# MiP_Mini-Pack.net
KiCad netlist of a schematic drawn in EAGLE
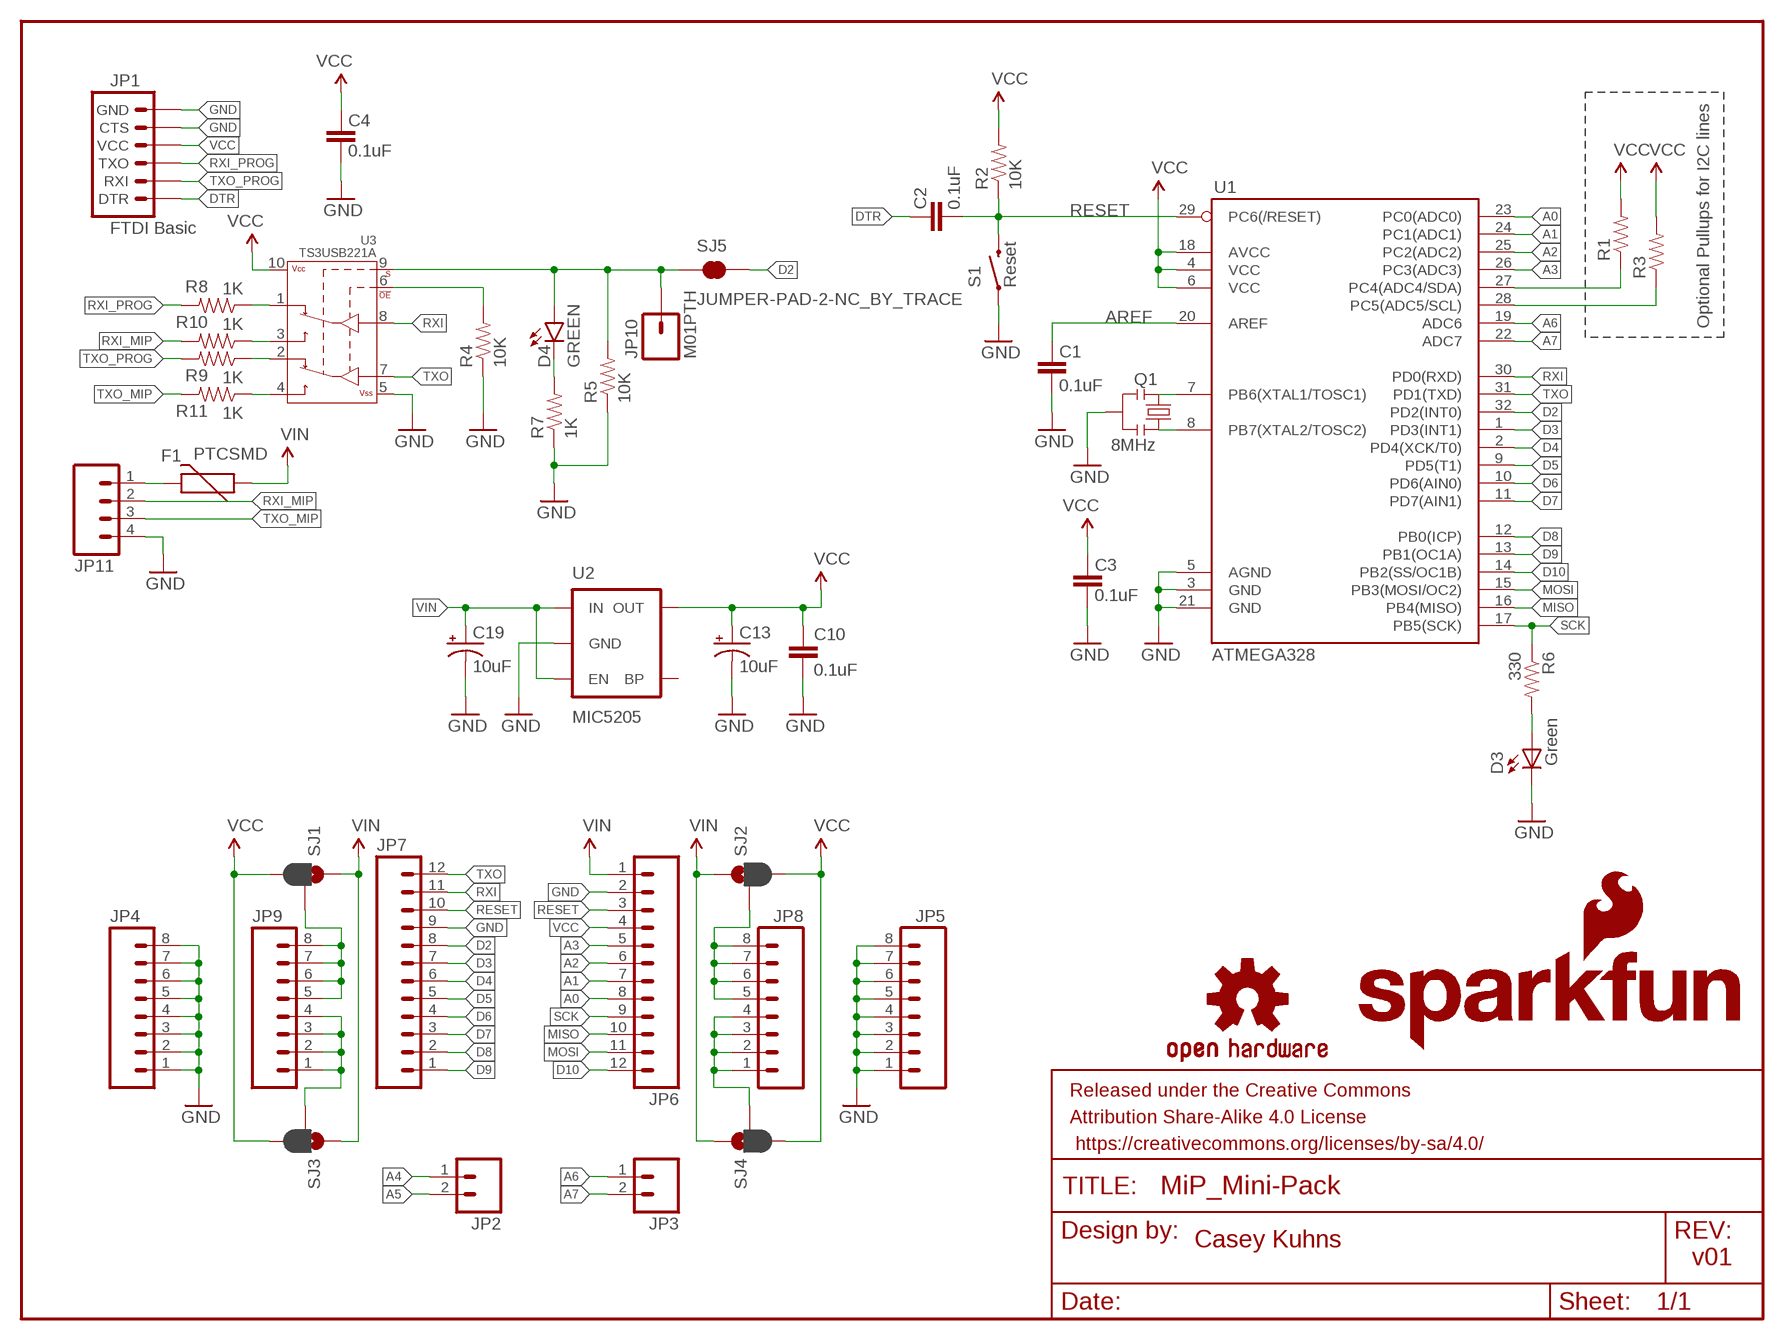
[diagram p0: schematic, sheet 1]

(export (version "E")
  (design (tool "Eeschema 10.0.6"))
  (components
    (comp (ref "C1")
      (value "0.1uF")
      (footprint "eagle-import:0603-CAP")
      (libsource (lib "eagle-import") (part "CAP0603-CAP"))
    )
    (comp (ref "C2")
      (value "0.1uF")
      (footprint "eagle-import:0603-CAP")
      (libsource (lib "eagle-import") (part "CAP0603-CAP"))
    )
    (comp (ref "C3")
      (value "0.1uF")
      (footprint "eagle-import:0603-CAP")
      (libsource (lib "eagle-import") (part "CAP0603-CAP"))
    )
    (comp (ref "C4")
      (value "0.1uF")
      (footprint "eagle-import:0603-CAP")
      (libsource (lib "eagle-import") (part "CAP0603-CAP"))
    )
    (comp (ref "C10")
      (value "0.1uF")
      (footprint "eagle-import:0603-CAP")
      (libsource (lib "eagle-import") (part "CAP0603-CAP"))
    )
    (comp (ref "C13")
      (value "10uF")
      (footprint "eagle-import:EIA3216")
      (libsource (lib "eagle-import") (part "CAP_POL1206"))
    )
    (comp (ref "C19")
      (value "10uF")
      (footprint "eagle-import:EIA3216")
      (libsource (lib "eagle-import") (part "CAP_POL1206"))
    )
    (comp (ref "D3")
      (value "Green")
      (footprint "eagle-import:0603-LED-ALT1")
      (libsource (lib "eagle-import") (part "LED"))
    )
    (comp (ref "D4")
      (value "GREEN")
      (footprint "eagle-import:LED-0603")
      (libsource (lib "eagle-import") (part "LED-GREEN0603"))
    )
    (comp (ref "F1")
      (value "PTCSMD")
      (footprint "eagle-import:PTC-1206")
      (libsource (lib "eagle-import") (part "PTCSMD"))
    )
    (comp (ref "FRAME1")
      (value "FRAME-LETTER")
      (footprint "eagle-import:CREATIVE_COMMONS")
      (libsource (lib "eagle-import") (part "FRAME-LETTER"))
    )
    (comp (ref "JP1")
      (value "FTDI Basic")
      (footprint "eagle-import:1X06")
      (libsource (lib "eagle-import") (part "ARDUINO_SERIAL_PROGRAMPTH"))
    )
    (comp (ref "JP2")
      (value "M02PTH")
      (footprint "eagle-import:1X02")
      (libsource (lib "eagle-import") (part "M02PTH"))
    )
    (comp (ref "JP3")
      (value "M02PTH")
      (footprint "eagle-import:1X02")
      (libsource (lib "eagle-import") (part "M02PTH"))
    )
    (comp (ref "JP4")
      (value "M081X08")
      (footprint "eagle-import:1X08")
      (libsource (lib "eagle-import") (part "M081X08"))
    )
    (comp (ref "JP5")
      (value "M081X08")
      (footprint "eagle-import:1X08")
      (libsource (lib "eagle-import") (part "M081X08"))
    )
    (comp (ref "JP6")
      (value "M12PTH")
      (footprint "eagle-import:1X12")
      (libsource (lib "eagle-import") (part "M12PTH"))
    )
    (comp (ref "JP7")
      (value "M12PTH")
      (footprint "eagle-import:1X12")
      (libsource (lib "eagle-import") (part "M12PTH"))
    )
    (comp (ref "JP8")
      (value "M081X08")
      (footprint "eagle-import:1X08")
      (libsource (lib "eagle-import") (part "M081X08"))
    )
    (comp (ref "JP9")
      (value "M081X08")
      (footprint "eagle-import:1X08")
      (libsource (lib "eagle-import") (part "M081X08"))
    )
    (comp (ref "JP10")
      (value "M01PTH")
      (footprint "eagle-import:1X01")
      (libsource (lib "eagle-import") (part "M01PTH"))
    )
    (comp (ref "JP11")
      (value "M04JST")
      (footprint "eagle-import:1X04-1.5MM_JST")
      (libsource (lib "eagle-import") (part "M04JST"))
    )
    (comp (ref "LOGO1")
      (value "SFE_LOGO_NAME_FLAME.1_INCH")
      (footprint "eagle-import:SFE_LOGO_NAME_FLAME_.1")
      (libsource (lib "eagle-import") (part "SFE_LOGO_NAME_FLAME.1_INCH"))
    )
    (comp (ref "LOGO2")
      (value "OSHW-LOGOS")
      (footprint "eagle-import:OSHW-LOGO-S")
      (libsource (lib "eagle-import") (part "OSHW-LOGOS"))
    )
    (comp (ref "Q1")
      (value "8MHz")
      (footprint "eagle-import:RESONATOR-SMD")
      (libsource (lib "eagle-import") (part "RESONATOR8MHZ"))
    )
    (comp (ref "R1")
      (value "RESISTOR0603-RES")
      (footprint "eagle-import:0603-RES")
      (libsource (lib "eagle-import") (part "RESISTOR0603-RES"))
    )
    (comp (ref "R2")
      (value "10K")
      (footprint "eagle-import:0603-RES")
      (libsource (lib "eagle-import") (part "RESISTOR0603-RES"))
    )
    (comp (ref "R3")
      (value "RESISTOR0603-RES")
      (footprint "eagle-import:0603-RES")
      (libsource (lib "eagle-import") (part "RESISTOR0603-RES"))
    )
    (comp (ref "R4")
      (value "10K")
      (footprint "eagle-import:0603-RES")
      (libsource (lib "eagle-import") (part "10KOHM1/10W1%(0603)0603"))
    )
    (comp (ref "R5")
      (value "10K")
      (footprint "eagle-import:0603-RES")
      (libsource (lib "eagle-import") (part "10KOHM1/10W1%(0603)0603"))
    )
    (comp (ref "R6")
      (value "330")
      (footprint "eagle-import:0603-RES")
      (libsource (lib "eagle-import") (part "RESISTOR0603-RES"))
    )
    (comp (ref "R7")
      (value "1K")
      (footprint "eagle-import:0603-RES")
      (libsource (lib "eagle-import") (part "1KOHM1/10W1%(0603)"))
    )
    (comp (ref "R8")
      (value "1K")
      (footprint "eagle-import:0603-RES")
      (libsource (lib "eagle-import") (part "1KOHM1/10W1%(0603)"))
    )
    (comp (ref "R9")
      (value "1K")
      (footprint "eagle-import:0603-RES")
      (libsource (lib "eagle-import") (part "1KOHM1/10W1%(0603)"))
    )
    (comp (ref "R10")
      (value "1K")
      (footprint "eagle-import:0603-RES")
      (libsource (lib "eagle-import") (part "1KOHM1/10W1%(0603)"))
    )
    (comp (ref "R11")
      (value "1K")
      (footprint "eagle-import:0603-RES")
      (libsource (lib "eagle-import") (part "1KOHM1/10W1%(0603)"))
    )
    (comp (ref "S1")
      (value "Reset")
      (footprint "eagle-import:TACTILE-SWITCH-SMD-ALT01")
      (libsource (lib "eagle-import") (part "SWITCH-MOMENTARY-2SMD-ALT01"))
    )
    (comp (ref "SJ1")
      (value "JUMPER-PAD-3-2OF3_NC_BY_PASTE")
      (footprint "eagle-import:PAD-JUMPER-3-2OF3_NC_BY_PASTE_YES_SILK_FULL_BOX")
      (libsource (lib "eagle-import") (part "JUMPER-PAD-3-2OF3_NC_BY_PASTE"))
    )
    (comp (ref "SJ2")
      (value "JUMPER-PAD-3-2OF3_NC_BY_PASTE")
      (footprint "eagle-import:PAD-JUMPER-3-2OF3_NC_BY_PASTE_YES_SILK_FULL_BOX")
      (libsource (lib "eagle-import") (part "JUMPER-PAD-3-2OF3_NC_BY_PASTE"))
    )
    (comp (ref "SJ3")
      (value "JUMPER-PAD-3-2OF3_NC_BY_PASTE")
      (footprint "eagle-import:PAD-JUMPER-3-2OF3_NC_BY_PASTE_YES_SILK_FULL_BOX")
      (libsource (lib "eagle-import") (part "JUMPER-PAD-3-2OF3_NC_BY_PASTE"))
    )
    (comp (ref "SJ4")
      (value "JUMPER-PAD-3-2OF3_NC_BY_PASTE")
      (footprint "eagle-import:PAD-JUMPER-3-2OF3_NC_BY_PASTE_YES_SILK_FULL_BOX")
      (libsource (lib "eagle-import") (part "JUMPER-PAD-3-2OF3_NC_BY_PASTE"))
    )
    (comp (ref "SJ5")
      (value "JUMPER-PAD-2-NC_BY_TRACE")
      (footprint "eagle-import:PAD-JUMPER-2-NC_BY_TRACE_YES_SILK")
      (libsource (lib "eagle-import") (part "JUMPER-PAD-2-NC_BY_TRACE"))
    )
    (comp (ref "U1")
      (value "ATMEGA328")
      (footprint "eagle-import:TQFP32-08")
      (libsource (lib "eagle-import") (part "ATMEGA168"))
    )
    (comp (ref "U2")
      (value "MIC5205")
      (footprint "eagle-import:SOT23-5")
      (libsource (lib "eagle-import") (part "V_REG_LDOSMD"))
    )
    (comp (ref "U3")
      (value "TS3USB221A")
      (footprint "eagle-import:QFN-10-RSE")
      (libsource (lib "eagle-import") (part "TS3USB221A"))
    )
  )
  (nets
    (net (code "1") (name "/AREF") (class "Default")
      (node (ref "C1") (pin "2") (pinfunction "2_2") (pintype "passive"))
      (node (ref "U1") (pin "20") (pinfunction "AREF_20") (pintype "bidirectional"))
    )
    (net (code "2") (name "A0") (class "Default")
      (node (ref "JP6") (pin "8") (pinfunction "8_8") (pintype "passive"))
      (node (ref "U1") (pin "23") (pinfunction "PC0(ADC0)_23") (pintype "bidirectional"))
    )
    (net (code "3") (name "A1") (class "Default")
      (node (ref "JP6") (pin "7") (pinfunction "7_7") (pintype "passive"))
      (node (ref "U1") (pin "24") (pinfunction "PC1(ADC1)_24") (pintype "bidirectional"))
    )
    (net (code "4") (name "A2") (class "Default")
      (node (ref "JP6") (pin "6") (pinfunction "6_6") (pintype "passive"))
      (node (ref "U1") (pin "25") (pinfunction "PC2(ADC2)_25") (pintype "bidirectional"))
    )
    (net (code "5") (name "A3") (class "Default")
      (node (ref "JP6") (pin "5") (pinfunction "5_5") (pintype "passive"))
      (node (ref "U1") (pin "26") (pinfunction "PC3(ADC3)_26") (pintype "bidirectional"))
    )
    (net (code "6") (name "A4") (class "Default")
      (node (ref "JP2") (pin "1") (pinfunction "1_1") (pintype "passive"))
      (node (ref "R1") (pin "1") (pinfunction "1_1") (pintype "passive"))
      (node (ref "U1") (pin "27") (pinfunction "PC4(ADC4/SDA)_27") (pintype "bidirectional"))
    )
    (net (code "7") (name "A5") (class "Default")
      (node (ref "JP2") (pin "2") (pinfunction "2_2") (pintype "passive"))
      (node (ref "R3") (pin "1") (pinfunction "1_1") (pintype "passive"))
      (node (ref "U1") (pin "28") (pinfunction "PC5(ADC5/SCL)_28") (pintype "bidirectional"))
    )
    (net (code "8") (name "A6") (class "Default")
      (node (ref "JP3") (pin "1") (pinfunction "1_1") (pintype "passive"))
      (node (ref "U1") (pin "19") (pinfunction "ADC6_19") (pintype "bidirectional"))
    )
    (net (code "9") (name "A7") (class "Default")
      (node (ref "JP3") (pin "2") (pinfunction "2_2") (pintype "passive"))
      (node (ref "U1") (pin "22") (pinfunction "ADC7_22") (pintype "bidirectional"))
    )
    (net (code "10") (name "D2") (class "Default")
      (node (ref "JP7") (pin "8") (pinfunction "8_8") (pintype "passive"))
      (node (ref "SJ5") (pin "2") (pinfunction "2_2") (pintype "passive"))
      (node (ref "U1") (pin "32") (pinfunction "PD2(INT0)_32") (pintype "bidirectional"))
    )
    (net (code "11") (name "D3") (class "Default")
      (node (ref "JP7") (pin "7") (pinfunction "7_7") (pintype "passive"))
      (node (ref "U1") (pin "1") (pinfunction "PD3(INT1)_1") (pintype "bidirectional"))
    )
    (net (code "12") (name "D4") (class "Default")
      (node (ref "JP7") (pin "6") (pinfunction "6_6") (pintype "passive"))
      (node (ref "U1") (pin "2") (pinfunction "PD4(XCK/T0)_2") (pintype "bidirectional"))
    )
    (net (code "13") (name "D5") (class "Default")
      (node (ref "JP7") (pin "5") (pinfunction "5_5") (pintype "passive"))
      (node (ref "U1") (pin "9") (pinfunction "PD5(T1)_9") (pintype "bidirectional"))
    )
    (net (code "14") (name "D6") (class "Default")
      (node (ref "JP7") (pin "4") (pinfunction "4_4") (pintype "passive"))
      (node (ref "U1") (pin "10") (pinfunction "PD6(AIN0)_10") (pintype "bidirectional"))
    )
    (net (code "15") (name "D7") (class "Default")
      (node (ref "JP7") (pin "3") (pinfunction "3_3") (pintype "passive"))
      (node (ref "U1") (pin "11") (pinfunction "PD7(AIN1)_11") (pintype "bidirectional"))
    )
    (net (code "16") (name "D8") (class "Default")
      (node (ref "JP7") (pin "2") (pinfunction "2_2") (pintype "passive"))
      (node (ref "U1") (pin "12") (pinfunction "PB0(ICP)_12") (pintype "bidirectional"))
    )
    (net (code "17") (name "D9") (class "Default")
      (node (ref "JP7") (pin "1") (pinfunction "1_1") (pintype "passive"))
      (node (ref "U1") (pin "13") (pinfunction "PB1(OC1A)_13") (pintype "bidirectional"))
    )
    (net (code "18") (name "D10") (class "Default")
      (node (ref "JP6") (pin "12") (pinfunction "12_12") (pintype "passive"))
      (node (ref "U1") (pin "14") (pinfunction "PB2(SS/OC1B)_14") (pintype "bidirectional"))
    )
    (net (code "19") (name "DTR") (class "Default")
      (node (ref "C2") (pin "2") (pinfunction "2_2") (pintype "passive"))
      (node (ref "JP1") (pin "1") (pinfunction "DTR_1") (pintype "passive"))
    )
    (net (code "20") (name "GND") (class "Default")
      (node (ref "C1") (pin "1") (pinfunction "1_1") (pintype "passive"))
      (node (ref "C10") (pin "2") (pinfunction "2_2") (pintype "passive"))
      (node (ref "C13") (pin "C") (pinfunction "-_C") (pintype "passive"))
      (node (ref "C19") (pin "C") (pinfunction "-_C") (pintype "passive"))
      (node (ref "C3") (pin "1") (pinfunction "1_1") (pintype "passive"))
      (node (ref "C4") (pin "1") (pinfunction "1_1") (pintype "passive"))
      (node (ref "D3") (pin "C") (pinfunction "C_C") (pintype "passive"))
      (node (ref "JP1") (pin "5") (pinfunction "CTS_5") (pintype "passive"))
      (node (ref "JP1") (pin "6") (pinfunction "GND_6") (pintype "passive"))
      (node (ref "JP11") (pin "4") (pinfunction "4_4") (pintype "passive"))
      (node (ref "JP4") (pin "1") (pinfunction "1_1") (pintype "passive"))
      (node (ref "JP4") (pin "2") (pinfunction "2_2") (pintype "passive"))
      (node (ref "JP4") (pin "3") (pinfunction "3_3") (pintype "passive"))
      (node (ref "JP4") (pin "4") (pinfunction "4_4") (pintype "passive"))
      (node (ref "JP4") (pin "5") (pinfunction "5_5") (pintype "passive"))
      (node (ref "JP4") (pin "6") (pinfunction "6_6") (pintype "passive"))
      (node (ref "JP4") (pin "7") (pinfunction "7_7") (pintype "passive"))
      (node (ref "JP4") (pin "8") (pinfunction "8_8") (pintype "passive"))
      (node (ref "JP5") (pin "1") (pinfunction "1_1") (pintype "passive"))
      (node (ref "JP5") (pin "2") (pinfunction "2_2") (pintype "passive"))
      (node (ref "JP5") (pin "3") (pinfunction "3_3") (pintype "passive"))
      (node (ref "JP5") (pin "4") (pinfunction "4_4") (pintype "passive"))
      (node (ref "JP5") (pin "5") (pinfunction "5_5") (pintype "passive"))
      (node (ref "JP5") (pin "6") (pinfunction "6_6") (pintype "passive"))
      (node (ref "JP5") (pin "7") (pinfunction "7_7") (pintype "passive"))
      (node (ref "JP5") (pin "8") (pinfunction "8_8") (pintype "passive"))
      (node (ref "JP6") (pin "2") (pinfunction "2_2") (pintype "passive"))
      (node (ref "JP7") (pin "9") (pinfunction "9_9") (pintype "passive"))
      (node (ref "Q1") (pin "2") (pinfunction "2_2") (pintype "passive"))
      (node (ref "R4") (pin "1") (pinfunction "1_1") (pintype "passive"))
      (node (ref "R5") (pin "1") (pinfunction "1_1") (pintype "passive"))
      (node (ref "R7") (pin "1") (pinfunction "1_1") (pintype "passive"))
      (node (ref "S1") (pin "1") (pinfunction "1_1") (pintype "passive"))
      (node (ref "S1") (pin "2") (pinfunction "1_2") (pintype "passive"))
      (node (ref "U1") (pin "21") (pinfunction "GND_21") (pintype "bidirectional"))
      (node (ref "U1") (pin "3") (pinfunction "GND_3") (pintype "bidirectional"))
      (node (ref "U1") (pin "5") (pinfunction "AGND_5") (pintype "bidirectional"))
      (node (ref "U2") (pin "2") (pinfunction "GND_2") (pintype "input"))
      (node (ref "U3") (pin "5") (pinfunction "VSS_5") (pintype "bidirectional"))
    )
    (net (code "21") (name "MISO") (class "Default")
      (node (ref "JP6") (pin "10") (pinfunction "10_10") (pintype "passive"))
      (node (ref "U1") (pin "16") (pinfunction "PB4(MISO)_16") (pintype "bidirectional"))
    )
    (net (code "22") (name "MOSI") (class "Default")
      (node (ref "JP6") (pin "11") (pinfunction "11_11") (pintype "passive"))
      (node (ref "U1") (pin "15") (pinfunction "PB3(MOSI/OC2)_15") (pintype "bidirectional"))
    )
    (net (code "23") (name "Net-(D3-PadA)") (class "Default")
      (node (ref "D3") (pin "A") (pinfunction "A_A") (pintype "passive"))
      (node (ref "R6") (pin "2") (pinfunction "2_2") (pintype "passive"))
    )
    (net (code "24") (name "Net-(D4-PadC)") (class "Default")
      (node (ref "D4") (pin "C") (pinfunction "C_C") (pintype "passive"))
      (node (ref "R7") (pin "2") (pinfunction "2_2") (pintype "passive"))
    )
    (net (code "25") (name "Net-(F1-Pad2)") (class "Default")
      (node (ref "F1") (pin "2") (pinfunction "2_2") (pintype "bidirectional"))
      (node (ref "JP11") (pin "1") (pinfunction "1_1") (pintype "passive"))
    )
    (net (code "26") (name "Net-(JP8-Pad1)") (class "Default")
      (node (ref "JP8") (pin "1") (pinfunction "1_1") (pintype "passive"))
      (node (ref "JP8") (pin "2") (pinfunction "2_2") (pintype "passive"))
      (node (ref "JP8") (pin "3") (pinfunction "3_3") (pintype "passive"))
      (node (ref "JP8") (pin "4") (pinfunction "4_4") (pintype "passive"))
      (node (ref "SJ4") (pin "2") (pinfunction "2_2") (pintype "passive"))
    )
    (net (code "27") (name "Net-(JP8-Pad5)") (class "Default")
      (node (ref "JP8") (pin "5") (pinfunction "5_5") (pintype "passive"))
      (node (ref "JP8") (pin "6") (pinfunction "6_6") (pintype "passive"))
      (node (ref "JP8") (pin "7") (pinfunction "7_7") (pintype "passive"))
      (node (ref "JP8") (pin "8") (pinfunction "8_8") (pintype "passive"))
      (node (ref "SJ2") (pin "2") (pinfunction "2_2") (pintype "passive"))
    )
    (net (code "28") (name "Net-(JP9-Pad1)") (class "Default")
      (node (ref "JP9") (pin "1") (pinfunction "1_1") (pintype "passive"))
      (node (ref "JP9") (pin "2") (pinfunction "2_2") (pintype "passive"))
      (node (ref "JP9") (pin "3") (pinfunction "3_3") (pintype "passive"))
      (node (ref "JP9") (pin "4") (pinfunction "4_4") (pintype "passive"))
      (node (ref "SJ3") (pin "2") (pinfunction "2_2") (pintype "passive"))
    )
    (net (code "29") (name "Net-(JP9-Pad5)") (class "Default")
      (node (ref "JP9") (pin "5") (pinfunction "5_5") (pintype "passive"))
      (node (ref "JP9") (pin "6") (pinfunction "6_6") (pintype "passive"))
      (node (ref "JP9") (pin "7") (pinfunction "7_7") (pintype "passive"))
      (node (ref "JP9") (pin "8") (pinfunction "8_8") (pintype "passive"))
      (node (ref "SJ1") (pin "2") (pinfunction "2_2") (pintype "passive"))
    )
    (net (code "30") (name "Net-(U1-PB6(XTAL1{slash}TOSC1))") (class "Default")
      (node (ref "Q1") (pin "1") (pinfunction "1_1") (pintype "passive"))
      (node (ref "U1") (pin "7") (pinfunction "PB6(XTAL1/TOSC1)_7") (pintype "bidirectional"))
    )
    (net (code "31") (name "Net-(U1-PB7(XTAL2{slash}TOSC2))") (class "Default")
      (node (ref "Q1") (pin "3") (pinfunction "3_3") (pintype "passive"))
      (node (ref "U1") (pin "8") (pinfunction "PB7(XTAL2/TOSC2)_8") (pintype "bidirectional"))
    )
    (net (code "32") (name "Net-(U3-1D+)") (class "Default")
      (node (ref "R8") (pin "1") (pinfunction "1_1") (pintype "passive"))
      (node (ref "U3") (pin "1") (pinfunction "1D+_1") (pintype "bidirectional"))
    )
    (net (code "33") (name "Net-(U3-1D-)") (class "Default")
      (node (ref "R9") (pin "1") (pinfunction "1_1") (pintype "passive"))
      (node (ref "U3") (pin "2") (pinfunction "1D-_2") (pintype "bidirectional"))
    )
    (net (code "34") (name "Net-(U3-2D+)") (class "Default")
      (node (ref "R10") (pin "1") (pinfunction "1_1") (pintype "passive"))
      (node (ref "U3") (pin "3") (pinfunction "2D+_3") (pintype "bidirectional"))
    )
    (net (code "35") (name "Net-(U3-2D-)") (class "Default")
      (node (ref "R11") (pin "1") (pinfunction "1_1") (pintype "passive"))
      (node (ref "U3") (pin "4") (pinfunction "2D-_4") (pintype "bidirectional"))
    )
    (net (code "36") (name "Net-(U3-S)") (class "Default")
      (node (ref "D4") (pin "A") (pinfunction "A_A") (pintype "passive"))
      (node (ref "JP10") (pin "1") (pinfunction "1_1") (pintype "passive"))
      (node (ref "R5") (pin "2") (pinfunction "2_2") (pintype "passive"))
      (node (ref "SJ5") (pin "1") (pinfunction "1_1") (pintype "passive"))
      (node (ref "U3") (pin "9") (pinfunction "S_9") (pintype "bidirectional"))
    )
    (net (code "37") (name "Net-(U3-~{OE})") (class "Default")
      (node (ref "R4") (pin "2") (pinfunction "2_2") (pintype "passive"))
      (node (ref "U3") (pin "6") (pinfunction "~{OE}_6") (pintype "bidirectional"))
    )
    (net (code "38") (name "RESET") (class "Default")
      (node (ref "C2") (pin "1") (pinfunction "1_1") (pintype "passive"))
      (node (ref "JP6") (pin "3") (pinfunction "3_3") (pintype "passive"))
      (node (ref "JP7") (pin "10") (pinfunction "10_10") (pintype "passive"))
      (node (ref "R2") (pin "1") (pinfunction "1_1") (pintype "passive"))
      (node (ref "S1") (pin "3") (pinfunction "2_3") (pintype "passive"))
      (node (ref "S1") (pin "4") (pinfunction "2_4") (pintype "passive"))
      (node (ref "U1") (pin "29") (pinfunction "PC6(/RESET)_29") (pintype "bidirectional"))
    )
    (net (code "39") (name "RXI") (class "Default")
      (node (ref "JP7") (pin "11") (pinfunction "11_11") (pintype "passive"))
      (node (ref "U1") (pin "30") (pinfunction "PD0(RXD)_30") (pintype "bidirectional"))
      (node (ref "U3") (pin "8") (pinfunction "D+_8") (pintype "bidirectional"))
    )
    (net (code "40") (name "RXI_MIP") (class "Default")
      (node (ref "JP11") (pin "2") (pinfunction "2_2") (pintype "passive"))
      (node (ref "R10") (pin "2") (pinfunction "2_2") (pintype "passive"))
    )
    (net (code "41") (name "RXI_PROG") (class "Default")
      (node (ref "JP1") (pin "3") (pinfunction "TXO_3") (pintype "passive"))
      (node (ref "R8") (pin "2") (pinfunction "2_2") (pintype "passive"))
    )
    (net (code "42") (name "SCK") (class "Default")
      (node (ref "JP6") (pin "9") (pinfunction "9_9") (pintype "passive"))
      (node (ref "R6") (pin "1") (pinfunction "1_1") (pintype "passive"))
      (node (ref "U1") (pin "17") (pinfunction "PB5(SCK)_17") (pintype "bidirectional"))
    )
    (net (code "43") (name "TXO") (class "Default")
      (node (ref "JP7") (pin "12") (pinfunction "12_12") (pintype "passive"))
      (node (ref "U1") (pin "31") (pinfunction "PD1(TXD)_31") (pintype "bidirectional"))
      (node (ref "U3") (pin "7") (pinfunction "D-_7") (pintype "bidirectional"))
    )
    (net (code "44") (name "TXO_MIP") (class "Default")
      (node (ref "JP11") (pin "3") (pinfunction "3_3") (pintype "passive"))
      (node (ref "R11") (pin "2") (pinfunction "2_2") (pintype "passive"))
    )
    (net (code "45") (name "TXO_PROG") (class "Default")
      (node (ref "JP1") (pin "2") (pinfunction "RXI_2") (pintype "passive"))
      (node (ref "R9") (pin "2") (pinfunction "2_2") (pintype "passive"))
    )
    (net (code "46") (name "VCC") (class "Default")
      (node (ref "C10") (pin "1") (pinfunction "1_1") (pintype "passive"))
      (node (ref "C13") (pin "A") (pinfunction "+_A") (pintype "passive"))
      (node (ref "C3") (pin "2") (pinfunction "2_2") (pintype "passive"))
      (node (ref "C4") (pin "2") (pinfunction "2_2") (pintype "passive"))
      (node (ref "JP1") (pin "4") (pinfunction "VCC_4") (pintype "passive"))
      (node (ref "JP6") (pin "4") (pinfunction "4_4") (pintype "passive"))
      (node (ref "R1") (pin "2") (pinfunction "2_2") (pintype "passive"))
      (node (ref "R2") (pin "2") (pinfunction "2_2") (pintype "passive"))
      (node (ref "R3") (pin "2") (pinfunction "2_2") (pintype "passive"))
      (node (ref "SJ1") (pin "3") (pinfunction "3_3") (pintype "passive"))
      (node (ref "SJ2") (pin "3") (pinfunction "3_3") (pintype "passive"))
      (node (ref "SJ3") (pin "3") (pinfunction "3_3") (pintype "passive"))
      (node (ref "SJ4") (pin "3") (pinfunction "3_3") (pintype "passive"))
      (node (ref "U1") (pin "18") (pinfunction "AVCC_18") (pintype "bidirectional"))
      (node (ref "U1") (pin "4") (pinfunction "VCC_4") (pintype "bidirectional"))
      (node (ref "U1") (pin "6") (pinfunction "VCC_6") (pintype "bidirectional"))
      (node (ref "U2") (pin "5") (pinfunction "OUT_5") (pintype "passive"))
      (node (ref "U3") (pin "10") (pinfunction "VCC_10") (pintype "bidirectional"))
    )
    (net (code "47") (name "VIN") (class "Default")
      (node (ref "C19") (pin "A") (pinfunction "+_A") (pintype "passive"))
      (node (ref "F1") (pin "1") (pinfunction "1_1") (pintype "bidirectional"))
      (node (ref "JP6") (pin "1") (pinfunction "1_1") (pintype "passive"))
      (node (ref "SJ1") (pin "1") (pinfunction "1_1") (pintype "passive"))
      (node (ref "SJ2") (pin "1") (pinfunction "1_1") (pintype "passive"))
      (node (ref "SJ3") (pin "1") (pinfunction "1_1") (pintype "passive"))
      (node (ref "SJ4") (pin "1") (pinfunction "1_1") (pintype "passive"))
      (node (ref "U2") (pin "1") (pinfunction "IN_1") (pintype "input"))
      (node (ref "U2") (pin "3") (pinfunction "EN_3") (pintype "input"))
    )
    (net (code "48") (name "unconnected-(U2-BP-Pad4)") (class "Default")
      (node (ref "U2") (pin "4") (pinfunction "BP_4") (pintype "input"))
    )
  )
)
